# main.net
KiCad netlist of a schematic drawn in EAGLE
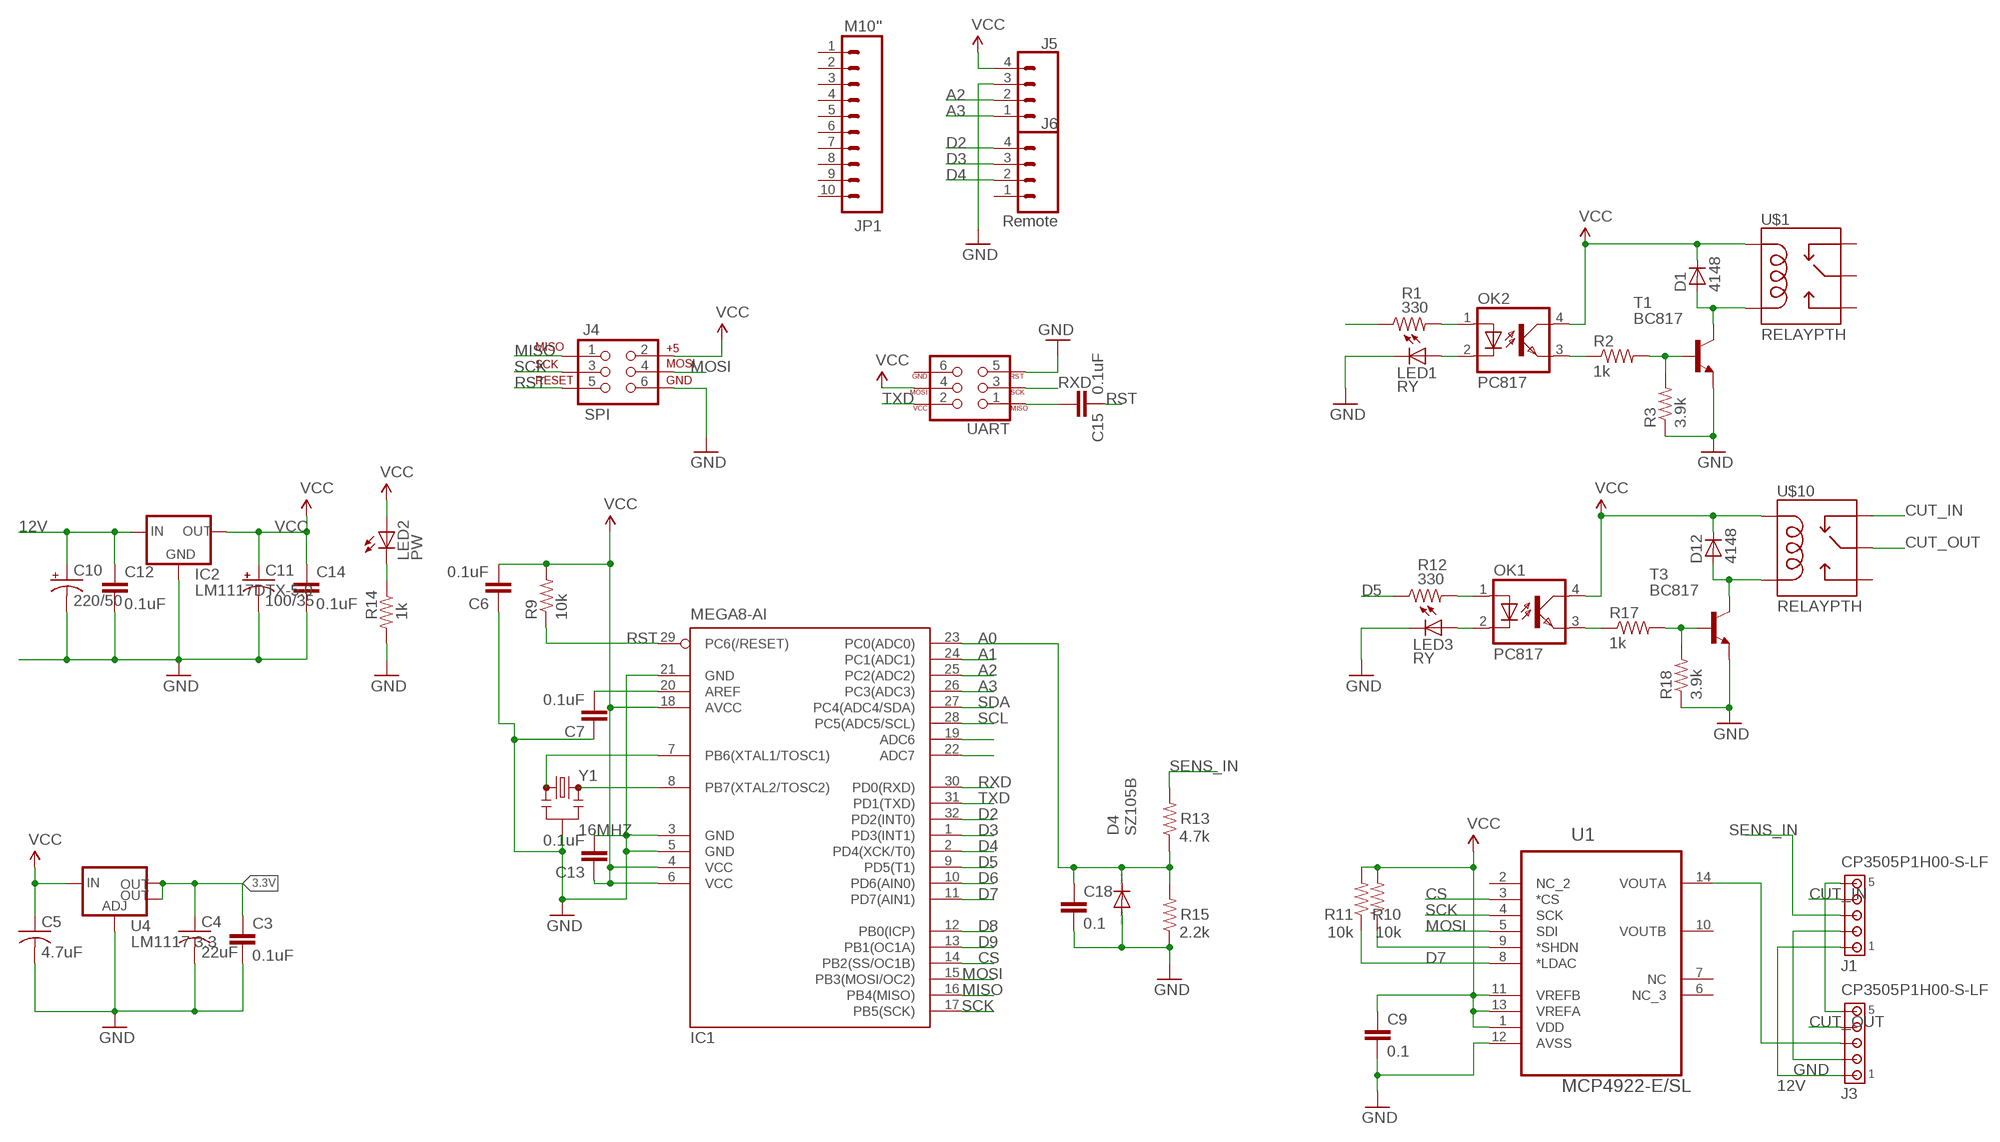
[diagram p0: schematic, sheet 1]

(export (version "E")
  (design (tool "Eeschema 10.0.6"))
  (components
    (comp (ref "C3")
      (value "0.1uF")
      (footprint "eagle-import:0805")
      (libsource (lib "eagle-import") (part "CAP0805"))
    )
    (comp (ref "C4")
      (value "22uF")
      (footprint "eagle-import:C1206")
      (libsource (lib "eagle-import") (part "C-USC1206"))
    )
    (comp (ref "C5")
      (value "4.7uF")
      (footprint "eagle-import:C1206")
      (libsource (lib "eagle-import") (part "C-USC1206"))
    )
    (comp (ref "C6")
      (value "0.1uF")
      (footprint "eagle-import:0805")
      (libsource (lib "eagle-import") (part "CAP0805"))
    )
    (comp (ref "C7")
      (value "0.1uF")
      (footprint "eagle-import:0805")
      (libsource (lib "eagle-import") (part "CAP0805"))
    )
    (comp (ref "C9")
      (value "0.1")
      (footprint "eagle-import:0805")
      (libsource (lib "eagle-import") (part "CAP0805"))
    )
    (comp (ref "C10")
      (value "220/50")
      (footprint "eagle-import:153CLV-1010")
      (libsource (lib "eagle-import") (part "CPOL-US153CLV-1010"))
    )
    (comp (ref "C11")
      (value "100/35")
      (footprint "eagle-import:153CLV-0605")
      (libsource (lib "eagle-import") (part "CPOL-US153CLV-0605"))
    )
    (comp (ref "C12")
      (value "0.1uF")
      (footprint "eagle-import:0805")
      (libsource (lib "eagle-import") (part "CAP0805"))
    )
    (comp (ref "C13")
      (value "0.1uF")
      (footprint "eagle-import:0805")
      (libsource (lib "eagle-import") (part "CAP0805"))
    )
    (comp (ref "C14")
      (value "0.1uF")
      (footprint "eagle-import:0805")
      (libsource (lib "eagle-import") (part "CAP0805"))
    )
    (comp (ref "C15")
      (value "0.1uF")
      (footprint "eagle-import:0805")
      (libsource (lib "eagle-import") (part "CAP0805"))
    )
    (comp (ref "C18")
      (value "0.1")
      (footprint "eagle-import:0805")
      (libsource (lib "eagle-import") (part "CAP0805"))
    )
    (comp (ref "D1")
      (value "4148")
      (footprint "eagle-import:SOD80")
      (libsource (lib "eagle-import") (part "D-SOD-80"))
    )
    (comp (ref "D4")
      (value "SZ105B")
      (footprint "eagle-import:DO-214AC")
      (libsource (lib "eagle-import") (part "DIODE-DO-214AC"))
    )
    (comp (ref "D12")
      (value "4148")
      (footprint "eagle-import:SOD80")
      (libsource (lib "eagle-import") (part "D-SOD-80"))
    )
    (comp (ref "IC1")
      (value "MEGA8-AI")
      (footprint "eagle-import:TQFP32-08")
      (fields (field (name "MPN") "ATMEGA8-16AU"))
      (libsource (lib "eagle-import") (part "MEGA8-AI"))
    )
    (comp (ref "IC2")
      (value "LM1117DTX-5.0")
      (footprint "eagle-import:TO252")
      (libsource (lib "eagle-import") (part "LM1117DTX-3.3"))
    )
    (comp (ref "J1")
      (value "CP3505P1H00-S-LF")
      (footprint "eagle-import:1445055-5")
      (libsource (lib "eagle-import") (part "1445055-5"))
    )
    (comp (ref "J3")
      (value "CP3505P1H00-S-LF")
      (footprint "eagle-import:1445055-5")
      (libsource (lib "eagle-import") (part "1445055-5"))
    )
    (comp (ref "J4")
      (value "SPI")
      (footprint "eagle-import:2X3")
      (libsource (lib "eagle-import") (part "AVR_SPI_PRG_6PTH"))
    )
    (comp (ref "J5")
      (value "CONN_04JST-PTH")
      (footprint "eagle-import:JST-4-PTH")
      (libsource (lib "eagle-import") (part "CONN_04JST-PTH"))
    )
    (comp (ref "J6")
      (value "Remote")
      (footprint "eagle-import:JST-4-PTH")
      (libsource (lib "eagle-import") (part "CONN_04JST-PTH"))
    )
    (comp (ref "JP1")
      (value "M10\"")
      (footprint "eagle-import:1X10")
      (libsource (lib "eagle-import") (part "M10{dblquote}"))
    )
    (comp (ref "LED1")
      (value "RY")
      (footprint "eagle-import:LED3MM")
      (libsource (lib "eagle-import") (part "LED3MM"))
    )
    (comp (ref "LED2")
      (value "PW")
      (footprint "eagle-import:LED3MM")
      (libsource (lib "eagle-import") (part "LED3MM"))
    )
    (comp (ref "LED3")
      (value "RY")
      (footprint "eagle-import:LED3MM")
      (libsource (lib "eagle-import") (part "LED3MM"))
    )
    (comp (ref "OK1")
      (value "PC817")
      (footprint "eagle-import:DIL4-SMD")
      (libsource (lib "eagle-import") (part "LTV816S"))
    )
    (comp (ref "OK2")
      (value "PC817")
      (footprint "eagle-import:DIL4-SMD")
      (libsource (lib "eagle-import") (part "LTV816S"))
    )
    (comp (ref "R1")
      (value "330")
      (footprint "eagle-import:0805")
      (libsource (lib "eagle-import") (part "RESISTOR0805-RES"))
    )
    (comp (ref "R2")
      (value "1k")
      (footprint "eagle-import:0805")
      (libsource (lib "eagle-import") (part "RESISTOR0805-RES"))
    )
    (comp (ref "R3")
      (value "3.9k")
      (footprint "eagle-import:0805")
      (libsource (lib "eagle-import") (part "RESISTOR0805-RES"))
    )
    (comp (ref "R9")
      (value "10k")
      (footprint "eagle-import:0805")
      (libsource (lib "eagle-import") (part "SparkFun-Resistors_RESISTOR0805-RES"))
    )
    (comp (ref "R10")
      (value "10k")
      (footprint "eagle-import:0805")
      (libsource (lib "eagle-import") (part "SparkFun-Resistors_RESISTOR0805-RES"))
    )
    (comp (ref "R11")
      (value "10k")
      (footprint "eagle-import:0805")
      (libsource (lib "eagle-import") (part "SparkFun-Resistors_RESISTOR0805-RES"))
    )
    (comp (ref "R12")
      (value "330")
      (footprint "eagle-import:0805")
      (libsource (lib "eagle-import") (part "RESISTOR0805-RES"))
    )
    (comp (ref "R13")
      (value "4.7k")
      (footprint "eagle-import:0805")
      (libsource (lib "eagle-import") (part "SparkFun-Resistors_RESISTOR0805-RES"))
    )
    (comp (ref "R14")
      (value "1k")
      (footprint "eagle-import:0805")
      (libsource (lib "eagle-import") (part "SparkFun-Resistors_RESISTOR0805-RES"))
    )
    (comp (ref "R15")
      (value "2.2k")
      (footprint "eagle-import:0805")
      (libsource (lib "eagle-import") (part "SparkFun-Resistors_RESISTOR0805-RES"))
    )
    (comp (ref "R17")
      (value "1k")
      (footprint "eagle-import:0805")
      (libsource (lib "eagle-import") (part "RESISTOR0805-RES"))
    )
    (comp (ref "R18")
      (value "3.9k")
      (footprint "eagle-import:0805")
      (libsource (lib "eagle-import") (part "RESISTOR0805-RES"))
    )
    (comp (ref "T1")
      (value "BC817")
      (footprint "eagle-import:SOT23-BEC")
      (libsource (lib "eagle-import") (part "-NPN-SOT23-BECBC817-16"))
    )
    (comp (ref "T3")
      (value "BC817")
      (footprint "eagle-import:SOT23-BEC")
      (libsource (lib "eagle-import") (part "-NPN-SOT23-BECBC817-16"))
    )
    (comp (ref "U$1")
      (value "RELAYPTH")
      (footprint "eagle-import:SRD-05VDC-SL-C")
      (libsource (lib "eagle-import") (part "RELAYPTH"))
    )
    (comp (ref "U$10")
      (value "RELAYPTH")
      (footprint "eagle-import:SRD-05VDC-SL-C")
      (libsource (lib "eagle-import") (part "RELAYPTH"))
    )
    (comp (ref "U1")
      (value "MCP4922-E/SL")
      (footprint "eagle-import:SOIC127P600X175-14N")
      (libsource (lib "eagle-import") (part "MCP4922-E/SL"))
    )
    (comp (ref "U4")
      (value "LM1117 3.3")
      (footprint "eagle-import:SOT223")
      (libsource (lib "eagle-import") (part "V_REG_LM1117SOT223"))
    )
    (comp (ref "UART")
      (value "AVR_SPI_PROG_3X2TESTPOINTS")
      (footprint "eagle-import:2X3_TEST_POINTS")
      (libsource (lib "eagle-import") (part "AVR_SPI_PROG_3X2TESTPOINTS"))
    )
    (comp (ref "Y1")
      (value "16MHZ")
      (footprint "eagle-import:RESONATOR-SMD")
      (libsource (lib "eagle-import") (part "RESONATOR16MHZ"))
    )
  )
  (nets
    (net (code "1") (name "/12V") (class "Default")
      (node (ref "C10") (pin "+") (pinfunction "+_+") (pintype "passive"))
      (node (ref "C12") (pin "1") (pinfunction "1_1") (pintype "passive"))
      (node (ref "IC2") (pin "2") (pinfunction "IN_2") (pintype "input"))
      (node (ref "J1") (pin "1") (pinfunction "1_1") (pintype "passive"))
      (node (ref "J3") (pin "1") (pinfunction "1_1") (pintype "passive"))
    )
    (net (code "2") (name "/A0") (class "Default")
      (node (ref "C18") (pin "1") (pinfunction "1_1") (pintype "passive"))
      (node (ref "D4") (pin "C") (pinfunction "C_C") (pintype "passive"))
      (node (ref "IC1") (pin "23") (pinfunction "PC0(ADC0)_23") (pintype "bidirectional"))
      (node (ref "R13") (pin "1") (pinfunction "1_1") (pintype "passive"))
      (node (ref "R15") (pin "2") (pinfunction "2_2") (pintype "passive"))
    )
    (net (code "3") (name "/A1") (class "Default")
      (node (ref "IC1") (pin "24") (pinfunction "PC1(ADC1)_24") (pintype "bidirectional"))
    )
    (net (code "4") (name "/A2") (class "Default")
      (node (ref "IC1") (pin "25") (pinfunction "PC2(ADC2)_25") (pintype "bidirectional"))
      (node (ref "J5") (pin "2") (pinfunction "2_2") (pintype "passive"))
    )
    (net (code "5") (name "/A3") (class "Default")
      (node (ref "IC1") (pin "26") (pinfunction "PC3(ADC3)_26") (pintype "bidirectional"))
      (node (ref "J5") (pin "1") (pinfunction "1_1") (pintype "passive"))
    )
    (net (code "6") (name "/CS") (class "Default")
      (node (ref "IC1") (pin "14") (pinfunction "PB2(SS/OC1B)_14") (pintype "bidirectional"))
      (node (ref "U1") (pin "3") (pinfunction "*CS_3") (pintype "input"))
    )
    (net (code "7") (name "/CUT_IN") (class "Default")
      (node (ref "J1") (pin "4") (pinfunction "4_4") (pintype "passive"))
      (node (ref "U$10") (pin "SWCLOSED") (pinfunction "SWCLOSE_SWCLOSED") (pintype "bidirectional"))
    )
    (net (code "8") (name "/CUT_OUT") (class "Default")
      (node (ref "J3") (pin "4") (pinfunction "4_4") (pintype "passive"))
      (node (ref "U$10") (pin "SWCOMMON") (pinfunction "SWCOMMON_SWCOMMON") (pintype "bidirectional"))
    )
    (net (code "9") (name "/D2") (class "Default")
      (node (ref "IC1") (pin "32") (pinfunction "PD2(INT0)_32") (pintype "bidirectional"))
      (node (ref "J6") (pin "4") (pinfunction "4_4") (pintype "passive"))
    )
    (net (code "10") (name "/D3") (class "Default")
      (node (ref "IC1") (pin "1") (pinfunction "PD3(INT1)_1") (pintype "bidirectional"))
      (node (ref "J6") (pin "3") (pinfunction "3_3") (pintype "passive"))
    )
    (net (code "11") (name "/D4") (class "Default")
      (node (ref "IC1") (pin "2") (pinfunction "PD4(XCK/T0)_2") (pintype "bidirectional"))
      (node (ref "J6") (pin "2") (pinfunction "2_2") (pintype "passive"))
    )
    (net (code "12") (name "/D5") (class "Default")
      (node (ref "IC1") (pin "9") (pinfunction "PD5(T1)_9") (pintype "bidirectional"))
      (node (ref "R1") (pin "1") (pinfunction "1_1") (pintype "passive"))
      (node (ref "R12") (pin "1") (pinfunction "1_1") (pintype "passive"))
    )
    (net (code "13") (name "/D6") (class "Default")
      (node (ref "IC1") (pin "10") (pinfunction "PD6(AIN0)_10") (pintype "bidirectional"))
    )
    (net (code "14") (name "/D7") (class "Default")
      (node (ref "IC1") (pin "11") (pinfunction "PD7(AIN1)_11") (pintype "bidirectional"))
      (node (ref "R11") (pin "1") (pinfunction "1_1") (pintype "passive"))
      (node (ref "U1") (pin "8") (pinfunction "*LDAC_8") (pintype "input"))
    )
    (net (code "15") (name "/D8") (class "Default")
      (node (ref "IC1") (pin "12") (pinfunction "PB0(ICP)_12") (pintype "bidirectional"))
    )
    (net (code "16") (name "/D9") (class "Default")
      (node (ref "IC1") (pin "13") (pinfunction "PB1(OC1A)_13") (pintype "bidirectional"))
    )
    (net (code "17") (name "/MISO") (class "Default")
      (node (ref "IC1") (pin "16") (pinfunction "PB4(MISO)_16") (pintype "bidirectional"))
      (node (ref "J4") (pin "1") (pinfunction "1_1") (pintype "passive"))
    )
    (net (code "18") (name "/MOSI") (class "Default")
      (node (ref "IC1") (pin "15") (pinfunction "PB3(MOSI/OC2)_15") (pintype "bidirectional"))
      (node (ref "J4") (pin "4") (pinfunction "4_4") (pintype "passive"))
      (node (ref "U1") (pin "5") (pinfunction "SDI_5") (pintype "input"))
    )
    (net (code "19") (name "/RST") (class "Default")
      (node (ref "C15") (pin "2") (pinfunction "2_2") (pintype "passive"))
      (node (ref "IC1") (pin "29") (pinfunction "PC6(/RESET)_29") (pintype "bidirectional"))
      (node (ref "J4") (pin "5") (pinfunction "5_5") (pintype "passive"))
      (node (ref "R9") (pin "1") (pinfunction "1_1") (pintype "passive"))
    )
    (net (code "20") (name "/RXD") (class "Default")
      (node (ref "IC1") (pin "30") (pinfunction "PD0(RXD)_30") (pintype "bidirectional"))
      (node (ref "UART") (pin "3") (pinfunction "3_3") (pintype "passive"))
    )
    (net (code "21") (name "/SCK") (class "Default")
      (node (ref "IC1") (pin "17") (pinfunction "PB5(SCK)_17") (pintype "bidirectional"))
      (node (ref "J4") (pin "3") (pinfunction "3_3") (pintype "passive"))
      (node (ref "U1") (pin "4") (pinfunction "SCK_4") (pintype "input"))
    )
    (net (code "22") (name "/SCL") (class "Default")
      (node (ref "IC1") (pin "28") (pinfunction "PC5(ADC5/SCL)_28") (pintype "bidirectional"))
    )
    (net (code "23") (name "/SDA") (class "Default")
      (node (ref "IC1") (pin "27") (pinfunction "PC4(ADC4/SDA)_27") (pintype "bidirectional"))
    )
    (net (code "24") (name "/SENS_IN") (class "Default")
      (node (ref "J1") (pin "3") (pinfunction "3_3") (pintype "passive"))
      (node (ref "R13") (pin "2") (pinfunction "2_2") (pintype "passive"))
    )
    (net (code "25") (name "/TXD") (class "Default")
      (node (ref "IC1") (pin "31") (pinfunction "PD1(TXD)_31") (pintype "bidirectional"))
      (node (ref "UART") (pin "2") (pinfunction "2_2") (pintype "passive"))
    )
    (net (code "26") (name "3.3V") (class "Default")
      (node (ref "C3") (pin "1") (pinfunction "1_1") (pintype "passive"))
      (node (ref "C4") (pin "1") (pinfunction "1_1") (pintype "passive"))
      (node (ref "U4") (pin "2") (pinfunction "OUT_2") (pintype "output"))
      (node (ref "U4") (pin "4") (pinfunction "OUT_4") (pintype "output"))
    )
    (net (code "27") (name "GND") (class "Default")
      (node (ref "C10") (pin "-") (pinfunction "-_-") (pintype "passive"))
      (node (ref "C11") (pin "-") (pinfunction "-_-") (pintype "passive"))
      (node (ref "C12") (pin "2") (pinfunction "2_2") (pintype "passive"))
      (node (ref "C13") (pin "2") (pinfunction "2_2") (pintype "passive"))
      (node (ref "C14") (pin "2") (pinfunction "2_2") (pintype "passive"))
      (node (ref "C18") (pin "2") (pinfunction "2_2") (pintype "passive"))
      (node (ref "C3") (pin "2") (pinfunction "2_2") (pintype "passive"))
      (node (ref "C4") (pin "2") (pinfunction "2_2") (pintype "passive"))
      (node (ref "C5") (pin "2") (pinfunction "2_2") (pintype "passive"))
      (node (ref "C6") (pin "1") (pinfunction "1_1") (pintype "passive"))
      (node (ref "C7") (pin "1") (pinfunction "1_1") (pintype "passive"))
      (node (ref "C9") (pin "2") (pinfunction "2_2") (pintype "passive"))
      (node (ref "D4") (pin "A") (pinfunction "A_A") (pintype "passive"))
      (node (ref "IC1") (pin "21") (pinfunction "GND_21") (pintype "power_in"))
      (node (ref "IC1") (pin "3") (pinfunction "GND_3") (pintype "power_in"))
      (node (ref "IC1") (pin "5") (pinfunction "GND_5") (pintype "power_in"))
      (node (ref "IC2") (pin "1") (pinfunction "GND_1") (pintype "input"))
      (node (ref "J1") (pin "2") (pinfunction "2_2") (pintype "passive"))
      (node (ref "J3") (pin "2") (pinfunction "2_2") (pintype "passive"))
      (node (ref "J4") (pin "6") (pinfunction "6_6") (pintype "passive"))
      (node (ref "J5") (pin "3") (pinfunction "3_3") (pintype "passive"))
      (node (ref "LED1") (pin "K") (pinfunction "C_K") (pintype "passive"))
      (node (ref "LED3") (pin "K") (pinfunction "C_K") (pintype "passive"))
      (node (ref "R14") (pin "2") (pinfunction "2_2") (pintype "passive"))
      (node (ref "R15") (pin "1") (pinfunction "1_1") (pintype "passive"))
      (node (ref "R18") (pin "1") (pinfunction "1_1") (pintype "passive"))
      (node (ref "R3") (pin "1") (pinfunction "1_1") (pintype "passive"))
      (node (ref "T1") (pin "E") (pinfunction "E_E") (pintype "passive"))
      (node (ref "T3") (pin "E") (pinfunction "E_E") (pintype "passive"))
      (node (ref "U1") (pin "12") (pinfunction "AVSS_12") (pintype "passive"))
      (node (ref "U4") (pin "1") (pinfunction "ADJ_1") (pintype "input"))
      (node (ref "UART") (pin "5") (pinfunction "5_5") (pintype "passive"))
      (node (ref "Y1") (pin "2") (pinfunction "2_2") (pintype "passive"))
    )
    (net (code "28") (name "Net-(C15-Pad1)") (class "Default")
      (node (ref "C15") (pin "1") (pinfunction "1_1") (pintype "passive"))
      (node (ref "UART") (pin "1") (pinfunction "1_1") (pintype "passive"))
    )
    (net (code "29") (name "Net-(D1-A)") (class "Default")
      (node (ref "D1") (pin "2") (pinfunction "A_2") (pintype "passive"))
      (node (ref "T1") (pin "C") (pinfunction "C_C") (pintype "passive"))
      (node (ref "U$1") (pin "COIL0") (pinfunction "COIL0_COIL0") (pintype "bidirectional"))
    )
    (net (code "30") (name "Net-(D12-A)") (class "Default")
      (node (ref "D12") (pin "2") (pinfunction "A_2") (pintype "passive"))
      (node (ref "T3") (pin "C") (pinfunction "C_C") (pintype "passive"))
      (node (ref "U$10") (pin "COIL0") (pinfunction "COIL0_COIL0") (pintype "bidirectional"))
    )
    (net (code "31") (name "Net-(IC1-AREF)") (class "Default")
      (node (ref "C7") (pin "2") (pinfunction "2_2") (pintype "passive"))
      (node (ref "IC1") (pin "20") (pinfunction "AREF_20") (pintype "passive"))
    )
    (net (code "32") (name "Net-(IC1-PB6(XTAL1{slash}TOSC1))") (class "Default")
      (node (ref "IC1") (pin "7") (pinfunction "PB6(XTAL1/TOSC1)_7") (pintype "bidirectional"))
      (node (ref "Y1") (pin "1") (pinfunction "1_1") (pintype "passive"))
    )
    (net (code "33") (name "Net-(IC1-PB7(XTAL2{slash}TOSC2))") (class "Default")
      (node (ref "IC1") (pin "8") (pinfunction "PB7(XTAL2/TOSC2)_8") (pintype "bidirectional"))
      (node (ref "Y1") (pin "3") (pinfunction "3_3") (pintype "passive"))
    )
    (net (code "34") (name "Net-(J1-Pad5)") (class "Default")
      (node (ref "J1") (pin "5") (pinfunction "5_5") (pintype "passive"))
      (node (ref "J3") (pin "5") (pinfunction "5_5") (pintype "passive"))
    )
    (net (code "35") (name "Net-(LED2-C)") (class "Default")
      (node (ref "LED2") (pin "K") (pinfunction "C_K") (pintype "passive"))
      (node (ref "R14") (pin "1") (pinfunction "1_1") (pintype "passive"))
    )
    (net (code "36") (name "Net-(OK1-A)") (class "Default")
      (node (ref "OK1") (pin "1") (pinfunction "A_1") (pintype "passive"))
      (node (ref "R12") (pin "2") (pinfunction "2_2") (pintype "passive"))
    )
    (net (code "37") (name "Net-(OK1-C)") (class "Default")
      (node (ref "LED3") (pin "A") (pinfunction "A_A") (pintype "passive"))
      (node (ref "OK1") (pin "2") (pinfunction "C_2") (pintype "passive"))
    )
    (net (code "38") (name "Net-(OK1-EMIT)") (class "Default")
      (node (ref "OK1") (pin "3") (pinfunction "EMIT_3") (pintype "passive"))
      (node (ref "R17") (pin "1") (pinfunction "1_1") (pintype "passive"))
    )
    (net (code "39") (name "Net-(OK2-A)") (class "Default")
      (node (ref "OK2") (pin "1") (pinfunction "A_1") (pintype "passive"))
      (node (ref "R1") (pin "2") (pinfunction "2_2") (pintype "passive"))
    )
    (net (code "40") (name "Net-(OK2-C)") (class "Default")
      (node (ref "LED1") (pin "A") (pinfunction "A_A") (pintype "passive"))
      (node (ref "OK2") (pin "2") (pinfunction "C_2") (pintype "passive"))
    )
    (net (code "41") (name "Net-(OK2-EMIT)") (class "Default")
      (node (ref "OK2") (pin "3") (pinfunction "EMIT_3") (pintype "passive"))
      (node (ref "R2") (pin "1") (pinfunction "1_1") (pintype "passive"))
    )
    (net (code "42") (name "Net-(R2-Pad2)") (class "Default")
      (node (ref "R2") (pin "2") (pinfunction "2_2") (pintype "passive"))
      (node (ref "R3") (pin "2") (pinfunction "2_2") (pintype "passive"))
      (node (ref "T1") (pin "B") (pinfunction "B_B") (pintype "passive"))
    )
    (net (code "43") (name "Net-(R17-Pad2)") (class "Default")
      (node (ref "R17") (pin "2") (pinfunction "2_2") (pintype "passive"))
      (node (ref "R18") (pin "2") (pinfunction "2_2") (pintype "passive"))
      (node (ref "T3") (pin "B") (pinfunction "B_B") (pintype "passive"))
    )
    (net (code "44") (name "Net-(U1-*SHDN)") (class "Default")
      (node (ref "R10") (pin "1") (pinfunction "1_1") (pintype "passive"))
      (node (ref "U1") (pin "9") (pinfunction "*SHDN_9") (pintype "input"))
    )
    (net (code "45") (name "Net-(U1-VOUTA)") (class "Default")
      (node (ref "J3") (pin "3") (pinfunction "3_3") (pintype "passive"))
      (node (ref "U1") (pin "14") (pinfunction "VOUTA_14") (pintype "output"))
    )
    (net (code "46") (name "VCC") (class "Default")
      (node (ref "C11") (pin "+") (pinfunction "+_+") (pintype "passive"))
      (node (ref "C13") (pin "1") (pinfunction "1_1") (pintype "passive"))
      (node (ref "C14") (pin "1") (pinfunction "1_1") (pintype "passive"))
      (node (ref "C5") (pin "1") (pinfunction "1_1") (pintype "passive"))
      (node (ref "C6") (pin "2") (pinfunction "2_2") (pintype "passive"))
      (node (ref "C9") (pin "1") (pinfunction "1_1") (pintype "passive"))
      (node (ref "D1") (pin "1") (pinfunction "C_1") (pintype "passive"))
      (node (ref "D12") (pin "1") (pinfunction "C_1") (pintype "passive"))
      (node (ref "IC1") (pin "18") (pinfunction "AVCC_18") (pintype "power_in"))
      (node (ref "IC1") (pin "4") (pinfunction "VCC_4") (pintype "power_in"))
      (node (ref "IC1") (pin "6") (pinfunction "VCC_6") (pintype "power_in"))
      (node (ref "IC2") (pin "TAB") (pinfunction "OUT_TAB") (pintype "passive"))
      (node (ref "J4") (pin "2") (pinfunction "2_2") (pintype "passive"))
      (node (ref "J5") (pin "4") (pinfunction "4_4") (pintype "passive"))
      (node (ref "LED2") (pin "A") (pinfunction "A_A") (pintype "passive"))
      (node (ref "OK1") (pin "4") (pinfunction "COL_4") (pintype "passive"))
      (node (ref "OK2") (pin "4") (pinfunction "COL_4") (pintype "passive"))
      (node (ref "R10") (pin "2") (pinfunction "2_2") (pintype "passive"))
      (node (ref "R11") (pin "2") (pinfunction "2_2") (pintype "passive"))
      (node (ref "R9") (pin "2") (pinfunction "2_2") (pintype "passive"))
      (node (ref "U$1") (pin "COIL1") (pinfunction "COIL1_COIL1") (pintype "bidirectional"))
      (node (ref "U$10") (pin "COIL1") (pinfunction "COIL1_COIL1") (pintype "bidirectional"))
      (node (ref "U1") (pin "1") (pinfunction "VDD_1") (pintype "power_in"))
      (node (ref "U1") (pin "11") (pinfunction "VREFB_11") (pintype "input"))
      (node (ref "U1") (pin "13") (pinfunction "VREFA_13") (pintype "input"))
      (node (ref "U4") (pin "3") (pinfunction "IN_3") (pintype "input"))
      (node (ref "UART") (pin "4") (pinfunction "4_4") (pintype "passive"))
    )
    (net (code "47") (name "unconnected-(IC1-ADC6-Pad19)") (class "Default")
      (node (ref "IC1") (pin "19") (pinfunction "ADC6_19") (pintype "bidirectional"))
    )
    (net (code "48") (name "unconnected-(IC1-ADC7-Pad22)") (class "Default")
      (node (ref "IC1") (pin "22") (pinfunction "ADC7_22") (pintype "bidirectional"))
    )
    (net (code "49") (name "unconnected-(J6-Pad1)") (class "Default")
      (node (ref "J6") (pin "1") (pinfunction "1_1") (pintype "passive"))
    )
    (net (code "50") (name "unconnected-(JP1-Pad1)") (class "Default")
      (node (ref "JP1") (pin "1") (pinfunction "1_1") (pintype "passive"))
    )
    (net (code "51") (name "unconnected-(JP1-Pad2)") (class "Default")
      (node (ref "JP1") (pin "2") (pinfunction "2_2") (pintype "passive"))
    )
    (net (code "52") (name "unconnected-(JP1-Pad3)") (class "Default")
      (node (ref "JP1") (pin "3") (pinfunction "3_3") (pintype "passive"))
    )
    (net (code "53") (name "unconnected-(JP1-Pad4)") (class "Default")
      (node (ref "JP1") (pin "4") (pinfunction "4_4") (pintype "passive"))
    )
    (net (code "54") (name "unconnected-(JP1-Pad5)") (class "Default")
      (node (ref "JP1") (pin "5") (pinfunction "5_5") (pintype "passive"))
    )
    (net (code "55") (name "unconnected-(JP1-Pad6)") (class "Default")
      (node (ref "JP1") (pin "6") (pinfunction "6_6") (pintype "passive"))
    )
    (net (code "56") (name "unconnected-(JP1-Pad7)") (class "Default")
      (node (ref "JP1") (pin "7") (pinfunction "7_7") (pintype "passive"))
    )
    (net (code "57") (name "unconnected-(JP1-Pad8)") (class "Default")
      (node (ref "JP1") (pin "8") (pinfunction "8_8") (pintype "passive"))
    )
    (net (code "58") (name "unconnected-(JP1-Pad9)") (class "Default")
      (node (ref "JP1") (pin "9") (pinfunction "9_9") (pintype "passive"))
    )
    (net (code "59") (name "unconnected-(JP1-Pad10)") (class "Default")
      (node (ref "JP1") (pin "10") (pinfunction "10_10") (pintype "passive"))
    )
    (net (code "60") (name "unconnected-(U$1-PadSWCOMMON)") (class "Default")
      (node (ref "U$1") (pin "SWCOMMON") (pinfunction "SWCOMMON_SWCOMMON") (pintype "bidirectional"))
    )
    (net (code "61") (name "unconnected-(U$1-PadSWOPEN)") (class "Default")
      (node (ref "U$1") (pin "SWOPEN") (pinfunction "SWOPEN_SWOPEN") (pintype "bidirectional"))
    )
    (net (code "62") (name "unconnected-(U$1-SWCLOSE-PadSWCLOSED)") (class "Default")
      (node (ref "U$1") (pin "SWCLOSED") (pinfunction "SWCLOSE_SWCLOSED") (pintype "bidirectional"))
    )
    (net (code "63") (name "unconnected-(U$10-PadSWOPEN)") (class "Default")
      (node (ref "U$10") (pin "SWOPEN") (pinfunction "SWOPEN_SWOPEN") (pintype "bidirectional"))
    )
    (net (code "64") (name "unconnected-(U1-NC-Pad7)") (class "Default")
      (node (ref "U1") (pin "7") (pinfunction "NC_7") (pintype "no_connect"))
    )
    (net (code "65") (name "unconnected-(U1-NC_2-Pad2)") (class "Default")
      (node (ref "U1") (pin "2") (pinfunction "NC_2_2") (pintype "no_connect"))
    )
    (net (code "66") (name "unconnected-(U1-NC_3-Pad6)") (class "Default")
      (node (ref "U1") (pin "6") (pinfunction "NC_3_6") (pintype "no_connect"))
    )
    (net (code "67") (name "unconnected-(U1-VOUTB-Pad10)") (class "Default")
      (node (ref "U1") (pin "10") (pinfunction "VOUTB_10") (pintype "output"))
    )
    (net (code "68") (name "unconnected-(UART-Pad6)") (class "Default")
      (node (ref "UART") (pin "6") (pinfunction "6_6") (pintype "passive"))
    )
  )
)
